# Focuser.net
KiCad netlist of a schematic drawn in EAGLE
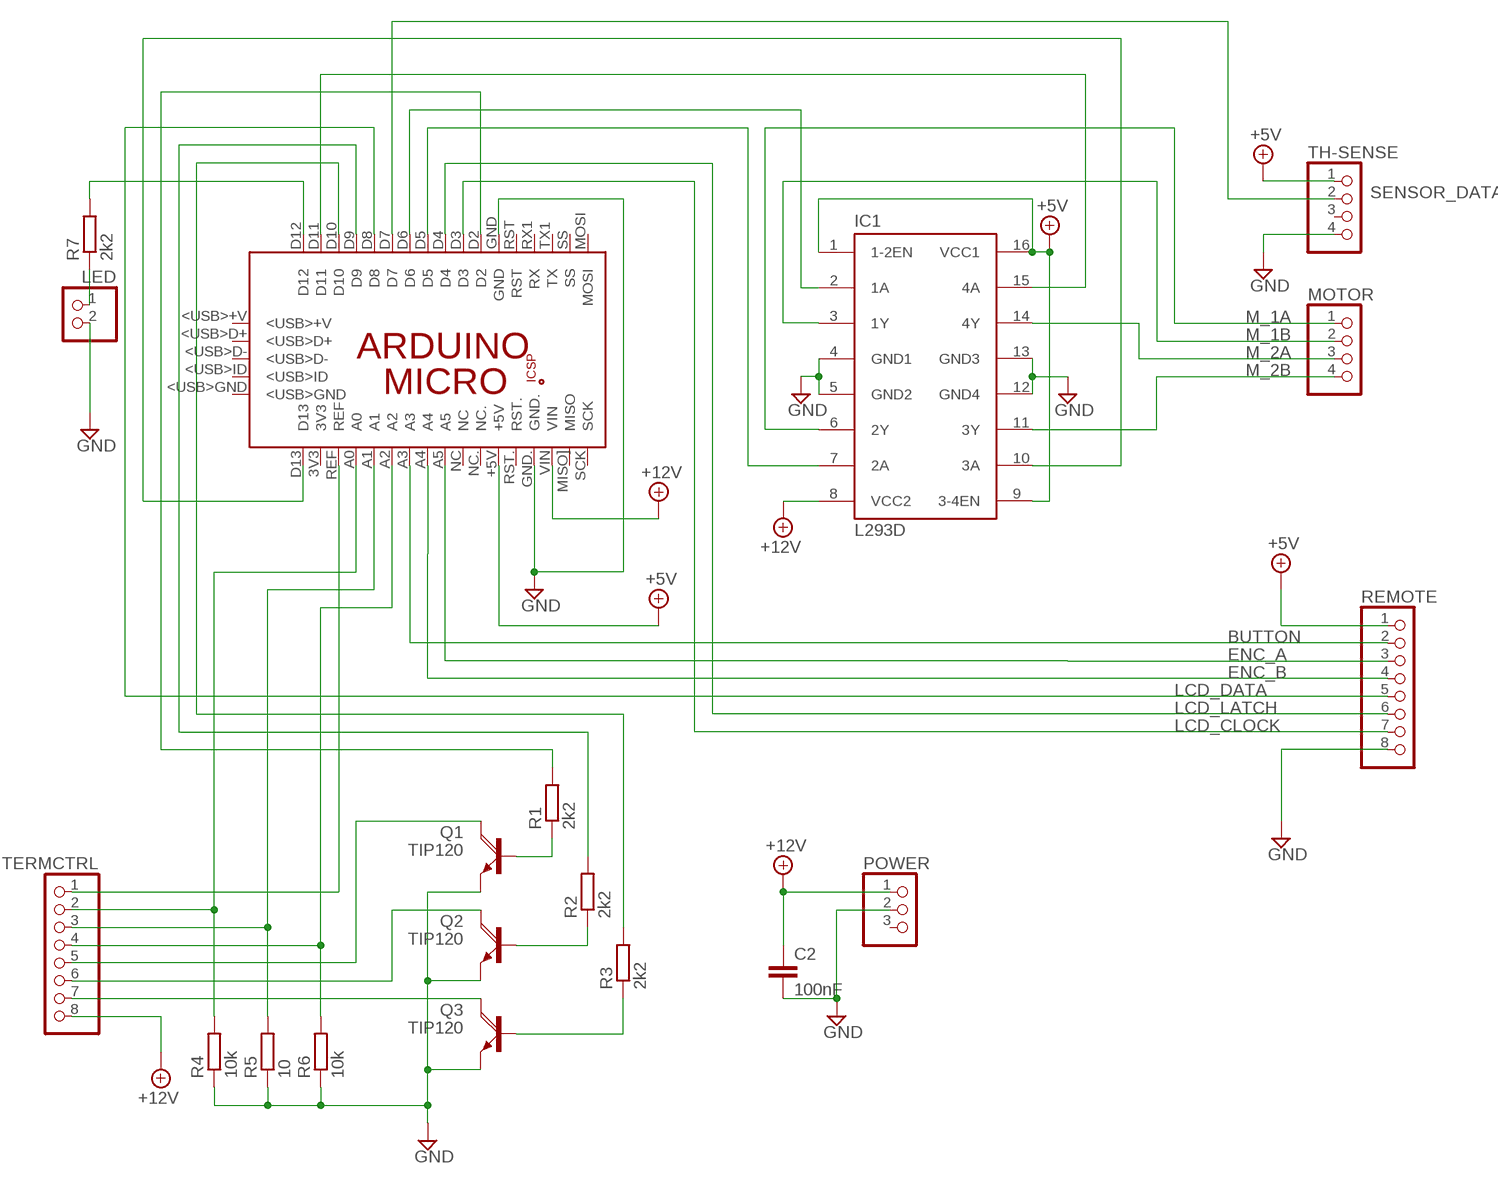
[diagram p0: schematic, sheet 1]

(export (version "E")
  (design (tool "Eeschema 10.0.6"))
  (components
    (comp (ref "C2")
      (value "100nF")
      (footprint "eagle-import:C025_050-025X075")
      (libsource (lib "eagle-import") (part "C-EU025_050-025X075"))
    )
    (comp (ref "IC1")
      (value "L293D")
      (footprint "eagle-import:DIL16")
      (libsource (lib "eagle-import") (part "L293D"))
    )
    (comp (ref "LED")
      (value "PINHD-1X2")
      (footprint "eagle-import:1X02")
      (libsource (lib "eagle-import") (part "PINHD-1X2"))
    )
    (comp (ref "MOTOR")
      (value "PINHD-1X4")
      (footprint "eagle-import:1X04")
      (libsource (lib "eagle-import") (part "PINHD-1X4"))
    )
    (comp (ref "PCB1")
      (value "ARDUINO_MICRO")
      (footprint "eagle-import:ARDUINO_MICRO")
      (libsource (lib "eagle-import") (part "ARDUINO_MICRO"))
    )
    (comp (ref "POWER")
      (value "PINHD-1X3")
      (footprint "eagle-import:1X03")
      (libsource (lib "eagle-import") (part "PINHD-1X3"))
    )
    (comp (ref "Q1")
      (value "TIP120")
      (footprint "eagle-import:TO220AH")
      (libsource (lib "eagle-import") (part "TIP120"))
    )
    (comp (ref "Q2")
      (value "TIP120")
      (footprint "eagle-import:TO220AH")
      (libsource (lib "eagle-import") (part "TIP120"))
    )
    (comp (ref "Q3")
      (value "TIP120")
      (footprint "eagle-import:TO220AH")
      (libsource (lib "eagle-import") (part "TIP120"))
    )
    (comp (ref "R1")
      (value "2k2")
      (footprint "eagle-import:0207_7")
      (libsource (lib "eagle-import") (part "R-EU_0207/7"))
    )
    (comp (ref "R2")
      (value "2k2")
      (footprint "eagle-import:0207_7")
      (libsource (lib "eagle-import") (part "R-EU_0207/7"))
    )
    (comp (ref "R3")
      (value "2k2")
      (footprint "eagle-import:0207_7")
      (libsource (lib "eagle-import") (part "R-EU_0207/7"))
    )
    (comp (ref "R4")
      (value "10k")
      (footprint "eagle-import:0207_7")
      (libsource (lib "eagle-import") (part "R-EU_0207/7"))
    )
    (comp (ref "R5")
      (value "10")
      (footprint "eagle-import:0207_7")
      (libsource (lib "eagle-import") (part "R-EU_0207/7"))
    )
    (comp (ref "R6")
      (value "10k")
      (footprint "eagle-import:0207_7")
      (libsource (lib "eagle-import") (part "R-EU_0207/7"))
    )
    (comp (ref "R7")
      (value "2k2")
      (footprint "eagle-import:0207_7")
      (libsource (lib "eagle-import") (part "R-EU_0207/7"))
    )
    (comp (ref "REMOTE")
      (value "PINHD-1X8")
      (footprint "eagle-import:1X08")
      (libsource (lib "eagle-import") (part "PINHD-1X8"))
    )
    (comp (ref "TERMCTRL")
      (value "PINHD-1X8")
      (footprint "eagle-import:1X08")
      (libsource (lib "eagle-import") (part "PINHD-1X8"))
    )
    (comp (ref "TH-SENSE")
      (value "PINHD-1X4")
      (footprint "eagle-import:1X04")
      (libsource (lib "eagle-import") (part "PINHD-1X4"))
    )
  )
  (nets
    (net (code "1") (name "+5V") (class "Default")
      (node (ref "IC1") (pin "1") (pinfunction "1-2EN_1") (pintype "input"))
      (node (ref "IC1") (pin "16") (pinfunction "VCC1_16") (pintype "power_in"))
      (node (ref "IC1") (pin "9") (pinfunction "3-4EN_9") (pintype "input"))
      (node (ref "PCB1") (pin "+5V") (pinfunction "+5V_+5V") (pintype "bidirectional"))
      (node (ref "REMOTE") (pin "1") (pinfunction "1_1") (pintype "passive"))
      (node (ref "TH-SENSE") (pin "1") (pinfunction "1_1") (pintype "passive"))
    )
    (net (code "2") (name "+12V") (class "Default")
      (node (ref "C2") (pin "1") (pinfunction "1_1") (pintype "passive"))
      (node (ref "IC1") (pin "8") (pinfunction "VCC2_8") (pintype "power_in"))
      (node (ref "PCB1") (pin "VIN") (pinfunction "VIN_VIN") (pintype "bidirectional"))
      (node (ref "POWER") (pin "1") (pinfunction "1_1") (pintype "passive"))
      (node (ref "TERMCTRL") (pin "8") (pinfunction "8_8") (pintype "passive"))
    )
    (net (code "3") (name "/BUTTON") (class "Default")
      (node (ref "PCB1") (pin "A3") (pinfunction "A3_A3") (pintype "bidirectional"))
      (node (ref "REMOTE") (pin "2") (pinfunction "2_2") (pintype "passive"))
    )
    (net (code "4") (name "/ENC_A") (class "Default")
      (node (ref "PCB1") (pin "A5") (pinfunction "A5_A5") (pintype "bidirectional"))
      (node (ref "REMOTE") (pin "3") (pinfunction "3_3") (pintype "passive"))
    )
    (net (code "5") (name "/ENC_B") (class "Default")
      (node (ref "PCB1") (pin "A4") (pinfunction "A4_A4") (pintype "bidirectional"))
      (node (ref "REMOTE") (pin "4") (pinfunction "4_4") (pintype "passive"))
    )
    (net (code "6") (name "/LCD_CLOCK") (class "Default")
      (node (ref "PCB1") (pin "D3") (pinfunction "D3_D3") (pintype "bidirectional"))
      (node (ref "REMOTE") (pin "7") (pinfunction "7_7") (pintype "passive"))
    )
    (net (code "7") (name "/LCD_DATA") (class "Default")
      (node (ref "PCB1") (pin "D8") (pinfunction "D8_D8") (pintype "bidirectional"))
      (node (ref "REMOTE") (pin "5") (pinfunction "5_5") (pintype "passive"))
    )
    (net (code "8") (name "/LCD_LATCH") (class "Default")
      (node (ref "PCB1") (pin "D4") (pinfunction "D4_D4") (pintype "bidirectional"))
      (node (ref "REMOTE") (pin "6") (pinfunction "6_6") (pintype "passive"))
    )
    (net (code "9") (name "/M_1A") (class "Default")
      (node (ref "IC1") (pin "6") (pinfunction "2Y_6") (pintype "output"))
      (node (ref "MOTOR") (pin "1") (pinfunction "1_1") (pintype "passive"))
    )
    (net (code "10") (name "/M_1B") (class "Default")
      (node (ref "IC1") (pin "3") (pinfunction "1Y_3") (pintype "output"))
      (node (ref "MOTOR") (pin "2") (pinfunction "2_2") (pintype "passive"))
    )
    (net (code "11") (name "/M_2A") (class "Default")
      (node (ref "IC1") (pin "14") (pinfunction "4Y_14") (pintype "output"))
      (node (ref "MOTOR") (pin "3") (pinfunction "3_3") (pintype "passive"))
    )
    (net (code "12") (name "/M_2B") (class "Default")
      (node (ref "IC1") (pin "11") (pinfunction "3Y_11") (pintype "output"))
      (node (ref "MOTOR") (pin "4") (pinfunction "4_4") (pintype "passive"))
    )
    (net (code "13") (name "/SENSOR_DATA") (class "Default")
      (node (ref "PCB1") (pin "D7") (pinfunction "D7_D7") (pintype "bidirectional"))
      (node (ref "TH-SENSE") (pin "2") (pinfunction "2_2") (pintype "passive"))
    )
    (net (code "14") (name "GND") (class "Default")
      (node (ref "C2") (pin "2") (pinfunction "2_2") (pintype "passive"))
      (node (ref "IC1") (pin "12") (pinfunction "GND4_12") (pintype "power_in"))
      (node (ref "IC1") (pin "13") (pinfunction "GND3_13") (pintype "power_in"))
      (node (ref "IC1") (pin "4") (pinfunction "GND1_4") (pintype "power_in"))
      (node (ref "IC1") (pin "5") (pinfunction "GND2_5") (pintype "power_in"))
      (node (ref "LED") (pin "2") (pinfunction "2_2") (pintype "passive"))
      (node (ref "PCB1") (pin "GND") (pinfunction "GND_GND") (pintype "bidirectional"))
      (node (ref "PCB1") (pin "GND.") (pinfunction "GND._GND.") (pintype "bidirectional"))
      (node (ref "POWER") (pin "2") (pinfunction "2_2") (pintype "passive"))
      (node (ref "Q1") (pin "E") (pinfunction "E_E") (pintype "passive"))
      (node (ref "Q2") (pin "E") (pinfunction "E_E") (pintype "passive"))
      (node (ref "Q3") (pin "E") (pinfunction "E_E") (pintype "passive"))
      (node (ref "R4") (pin "1") (pinfunction "1_1") (pintype "passive"))
      (node (ref "R5") (pin "1") (pinfunction "1_1") (pintype "passive"))
      (node (ref "R6") (pin "1") (pinfunction "1_1") (pintype "passive"))
      (node (ref "REMOTE") (pin "8") (pinfunction "8_8") (pintype "passive"))
      (node (ref "TH-SENSE") (pin "4") (pinfunction "4_4") (pintype "passive"))
    )
    (net (code "15") (name "Net-(IC1-1A)") (class "Default")
      (node (ref "IC1") (pin "2") (pinfunction "1A_2") (pintype "input"))
      (node (ref "PCB1") (pin "D6") (pinfunction "D6_D6") (pintype "bidirectional"))
    )
    (net (code "16") (name "Net-(IC1-2A)") (class "Default")
      (node (ref "IC1") (pin "7") (pinfunction "2A_7") (pintype "input"))
      (node (ref "PCB1") (pin "D5") (pinfunction "D5_D5") (pintype "bidirectional"))
    )
    (net (code "17") (name "Net-(IC1-3A)") (class "Default")
      (node (ref "IC1") (pin "10") (pinfunction "3A_10") (pintype "input"))
      (node (ref "PCB1") (pin "D13") (pinfunction "D13_D13") (pintype "bidirectional"))
    )
    (net (code "18") (name "Net-(IC1-4A)") (class "Default")
      (node (ref "IC1") (pin "15") (pinfunction "4A_15") (pintype "input"))
      (node (ref "PCB1") (pin "D11") (pinfunction "D11_D11") (pintype "bidirectional"))
    )
    (net (code "19") (name "Net-(LED-Pad1)") (class "Default")
      (node (ref "LED") (pin "1") (pinfunction "1_1") (pintype "passive"))
      (node (ref "R7") (pin "1") (pinfunction "1_1") (pintype "passive"))
    )
    (net (code "20") (name "Net-(PCB1-PadA0)") (class "Default")
      (node (ref "PCB1") (pin "A0") (pinfunction "A0_A0") (pintype "bidirectional"))
      (node (ref "R4") (pin "2") (pinfunction "2_2") (pintype "passive"))
      (node (ref "TERMCTRL") (pin "2") (pinfunction "2_2") (pintype "passive"))
    )
    (net (code "21") (name "Net-(PCB1-PadA1)") (class "Default")
      (node (ref "PCB1") (pin "A1") (pinfunction "A1_A1") (pintype "bidirectional"))
      (node (ref "R5") (pin "2") (pinfunction "2_2") (pintype "passive"))
      (node (ref "TERMCTRL") (pin "3") (pinfunction "3_3") (pintype "passive"))
    )
    (net (code "22") (name "Net-(PCB1-PadA2)") (class "Default")
      (node (ref "PCB1") (pin "A2") (pinfunction "A2_A2") (pintype "bidirectional"))
      (node (ref "R6") (pin "2") (pinfunction "2_2") (pintype "passive"))
      (node (ref "TERMCTRL") (pin "4") (pinfunction "4_4") (pintype "passive"))
    )
    (net (code "23") (name "Net-(PCB1-PadD2)") (class "Default")
      (node (ref "PCB1") (pin "D2") (pinfunction "D2_D2") (pintype "bidirectional"))
      (node (ref "R1") (pin "2") (pinfunction "2_2") (pintype "passive"))
    )
    (net (code "24") (name "Net-(PCB1-PadD9)") (class "Default")
      (node (ref "PCB1") (pin "D9") (pinfunction "D9_D9") (pintype "bidirectional"))
      (node (ref "R2") (pin "2") (pinfunction "2_2") (pintype "passive"))
    )
    (net (code "25") (name "Net-(PCB1-PadD10)") (class "Default")
      (node (ref "PCB1") (pin "D10") (pinfunction "D10_D10") (pintype "bidirectional"))
      (node (ref "R3") (pin "2") (pinfunction "2_2") (pintype "passive"))
    )
    (net (code "26") (name "Net-(PCB1-PadD12)") (class "Default")
      (node (ref "PCB1") (pin "D12") (pinfunction "D12_D12") (pintype "bidirectional"))
      (node (ref "R7") (pin "2") (pinfunction "2_2") (pintype "passive"))
    )
    (net (code "27") (name "Net-(PCB1-PadREF)") (class "Default")
      (node (ref "PCB1") (pin "REF") (pinfunction "REF_REF") (pintype "bidirectional"))
      (node (ref "TERMCTRL") (pin "1") (pinfunction "1_1") (pintype "passive"))
    )
    (net (code "28") (name "Net-(Q1-PadB)") (class "Default")
      (node (ref "Q1") (pin "B") (pinfunction "B_B") (pintype "passive"))
      (node (ref "R1") (pin "1") (pinfunction "1_1") (pintype "passive"))
    )
    (net (code "29") (name "Net-(Q1-PadC)") (class "Default")
      (node (ref "Q1") (pin "C") (pinfunction "C_C") (pintype "passive"))
      (node (ref "TERMCTRL") (pin "5") (pinfunction "5_5") (pintype "passive"))
    )
    (net (code "30") (name "Net-(Q2-PadB)") (class "Default")
      (node (ref "Q2") (pin "B") (pinfunction "B_B") (pintype "passive"))
      (node (ref "R2") (pin "1") (pinfunction "1_1") (pintype "passive"))
    )
    (net (code "31") (name "Net-(Q2-PadC)") (class "Default")
      (node (ref "Q2") (pin "C") (pinfunction "C_C") (pintype "passive"))
      (node (ref "TERMCTRL") (pin "6") (pinfunction "6_6") (pintype "passive"))
    )
    (net (code "32") (name "Net-(Q3-PadB)") (class "Default")
      (node (ref "Q3") (pin "B") (pinfunction "B_B") (pintype "passive"))
      (node (ref "R3") (pin "1") (pinfunction "1_1") (pintype "passive"))
    )
    (net (code "33") (name "Net-(Q3-PadC)") (class "Default")
      (node (ref "Q3") (pin "C") (pinfunction "C_C") (pintype "passive"))
      (node (ref "TERMCTRL") (pin "7") (pinfunction "7_7") (pintype "passive"))
    )
    (net (code "34") (name "unconnected-(PCB1-MISO-PadMISO])") (class "Default")
      (node (ref "PCB1") (pin "MISO]") (pinfunction "MISO_MISO]") (pintype "bidirectional"))
    )
    (net (code "35") (name "unconnected-(PCB1-Pad3V3)") (class "Default")
      (node (ref "PCB1") (pin "3V3") (pinfunction "3V3_3V3") (pintype "bidirectional"))
    )
    (net (code "36") (name "unconnected-(PCB1-Pad5V)") (class "Default")
      (node (ref "PCB1") (pin "5V") (pinfunction "5V_5V") (pintype "bidirectional"))
    )
    (net (code "37") (name "unconnected-(PCB1-Pad<USB>+V)") (class "Default")
      (node (ref "PCB1") (pin "<USB>+V") (pinfunction "<USB>+V_<USB>+V") (pintype "bidirectional"))
    )
    (net (code "38") (name "unconnected-(PCB1-Pad<USB>D+)") (class "Default")
      (node (ref "PCB1") (pin "<USB>D+") (pinfunction "<USB>D+_<USB>D+") (pintype "bidirectional"))
    )
    (net (code "39") (name "unconnected-(PCB1-Pad<USB>D-)") (class "Default")
      (node (ref "PCB1") (pin "<USB>D-") (pinfunction "<USB>D-_<USB>D-") (pintype "bidirectional"))
    )
    (net (code "40") (name "unconnected-(PCB1-Pad<USB>GND)") (class "Default")
      (node (ref "PCB1") (pin "<USB>GND") (pinfunction "<USB>GND_<USB>GND") (pintype "bidirectional"))
    )
    (net (code "41") (name "unconnected-(PCB1-Pad<USB>ID)") (class "Default")
      (node (ref "PCB1") (pin "<USB>ID") (pinfunction "<USB>ID_<USB>ID") (pintype "bidirectional"))
    )
    (net (code "42") (name "unconnected-(PCB1-PadGND_)") (class "Default")
      (node (ref "PCB1") (pin "GND_") (pinfunction "GND__GND_") (pintype "bidirectional"))
    )
    (net (code "43") (name "unconnected-(PCB1-PadMISO.)") (class "Default")
      (node (ref "PCB1") (pin "MISO.") (pinfunction "MISO._MISO.") (pintype "bidirectional"))
    )
    (net (code "44") (name "unconnected-(PCB1-PadMOSI)") (class "Default")
      (node (ref "PCB1") (pin "MOSI") (pinfunction "MOSI_MOSI") (pintype "bidirectional"))
    )
    (net (code "45") (name "unconnected-(PCB1-PadMOSI.)") (class "Default")
      (node (ref "PCB1") (pin "MOSI.") (pinfunction "MOSI._MOSI.") (pintype "bidirectional"))
    )
    (net (code "46") (name "unconnected-(PCB1-PadNC)") (class "Default")
      (node (ref "PCB1") (pin "NC") (pinfunction "NC_NC") (pintype "bidirectional"))
    )
    (net (code "47") (name "unconnected-(PCB1-PadNC.)") (class "Default")
      (node (ref "PCB1") (pin "NC.") (pinfunction "NC._NC.") (pintype "bidirectional"))
    )
    (net (code "48") (name "unconnected-(PCB1-PadRESET..)") (class "Default")
      (node (ref "PCB1") (pin "RESET..") (pinfunction "RESET.._RESET..") (pintype "bidirectional"))
    )
    (net (code "49") (name "unconnected-(PCB1-PadRST)") (class "Default")
      (node (ref "PCB1") (pin "RST") (pinfunction "RST_RST") (pintype "bidirectional"))
    )
    (net (code "50") (name "unconnected-(PCB1-PadRST.)") (class "Default")
      (node (ref "PCB1") (pin "RST.") (pinfunction "RST._RST.") (pintype "bidirectional"))
    )
    (net (code "51") (name "unconnected-(PCB1-PadSCK)") (class "Default")
      (node (ref "PCB1") (pin "SCK") (pinfunction "SCK_SCK") (pintype "bidirectional"))
    )
    (net (code "52") (name "unconnected-(PCB1-PadSCK.)") (class "Default")
      (node (ref "PCB1") (pin "SCK.") (pinfunction "SCK._SCK.") (pintype "bidirectional"))
    )
    (net (code "53") (name "unconnected-(PCB1-PadSS)") (class "Default")
      (node (ref "PCB1") (pin "SS") (pinfunction "SS_SS") (pintype "bidirectional"))
    )
    (net (code "54") (name "unconnected-(PCB1-RX-PadRX1)") (class "Default")
      (node (ref "PCB1") (pin "RX1") (pinfunction "RX_RX1") (pintype "bidirectional"))
    )
    (net (code "55") (name "unconnected-(PCB1-TX-PadTX1)") (class "Default")
      (node (ref "PCB1") (pin "TX1") (pinfunction "TX_TX1") (pintype "bidirectional"))
    )
    (net (code "56") (name "unconnected-(POWER-Pad3)") (class "Default")
      (node (ref "POWER") (pin "3") (pinfunction "3_3") (pintype "passive"))
    )
    (net (code "57") (name "unconnected-(TH-SENSE-Pad3)") (class "Default")
      (node (ref "TH-SENSE") (pin "3") (pinfunction "3_3") (pintype "passive"))
    )
  )
)
